# Adafruit_bicolor_8x8.net
KiCad netlist of a schematic drawn in EAGLE
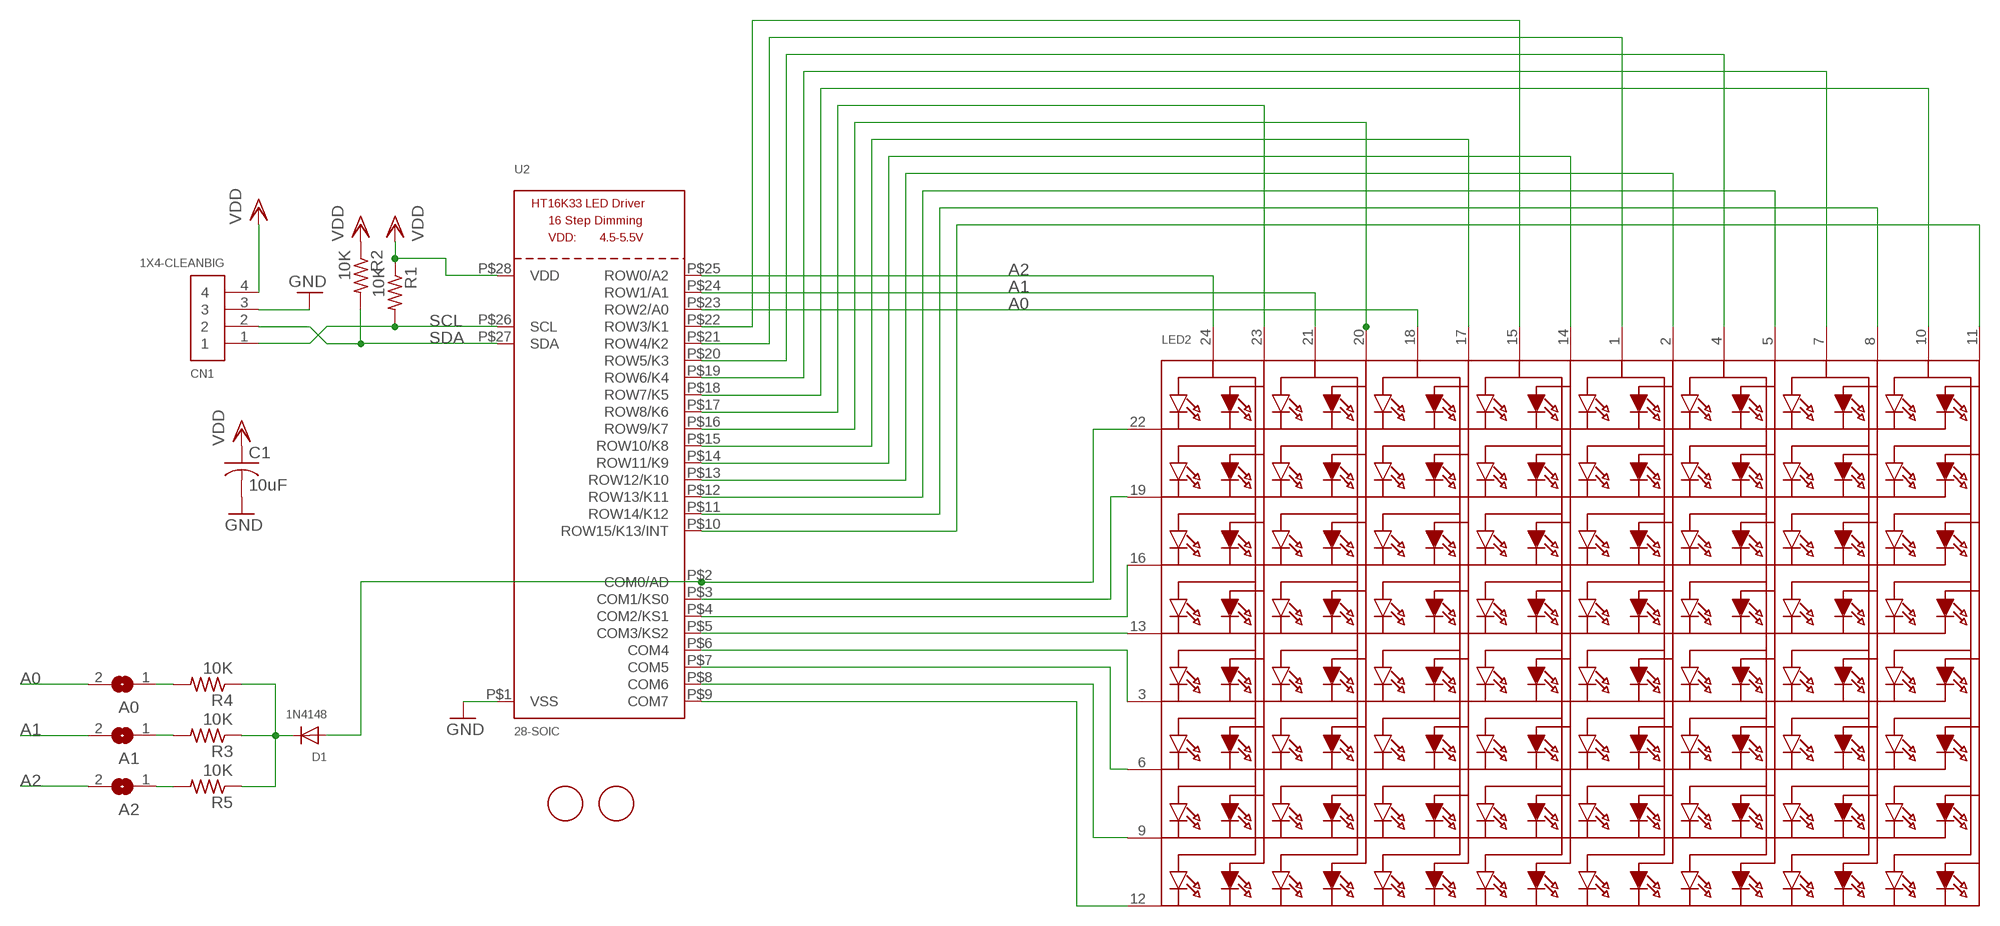
[diagram p0: schematic, sheet 1]

(export (version "E")
  (design (tool "Eeschema 10.0.6"))
  (components
    (comp (ref "A0")
      (value "SOLDERJUMPERREFLOW_NOPASTE")
      (footprint "eagle-import:SOLDERJUMPER_REFLOW_NOPASTE")
      (libsource (lib "eagle-import") (part "SOLDERJUMPERREFLOW_NOPASTE"))
    )
    (comp (ref "A1")
      (value "SOLDERJUMPERREFLOW_NOPASTE")
      (footprint "eagle-import:SOLDERJUMPER_REFLOW_NOPASTE")
      (libsource (lib "eagle-import") (part "SOLDERJUMPERREFLOW_NOPASTE"))
    )
    (comp (ref "A2")
      (value "SOLDERJUMPERREFLOW_NOPASTE")
      (footprint "eagle-import:SOLDERJUMPER_REFLOW_NOPASTE")
      (libsource (lib "eagle-import") (part "SOLDERJUMPERREFLOW_NOPASTE"))
    )
    (comp (ref "C1")
      (value "10uF")
      (footprint "eagle-import:C0805")
      (libsource (lib "eagle-import") (part "C-USC0805"))
    )
    (comp (ref "CN1")
      (value "1X4-CLEANBIG")
      (footprint "eagle-import:1X04-CLEANBIG")
      (libsource (lib "eagle-import") (part "1X4-CLEANBIG"))
    )
    (comp (ref "D1")
      (value "1N4148")
      (footprint "eagle-import:SOD-323F")
      (libsource (lib "eagle-import") (part "DIODESOD-323F"))
    )
    (comp (ref "LED2")
      (value "DISP_SEGMENT_8X8_BICOLOR_ROWCATHODEMI2A883XX")
      (footprint "eagle-import:SEGMENT_BICOL_BL-M12A883XX")
      (libsource (lib "eagle-import") (part "DISP_SEGMENT_8X8_BICOLOR_ROWCATHODEMI2A883XX"))
    )
    (comp (ref "R1")
      (value "10K")
      (footprint "eagle-import:R0805")
      (libsource (lib "eagle-import") (part "R-US_R0805"))
    )
    (comp (ref "R2")
      (value "10K")
      (footprint "eagle-import:R0805")
      (libsource (lib "eagle-import") (part "R-US_R0805"))
    )
    (comp (ref "R3")
      (value "10K")
      (footprint "eagle-import:R0805")
      (libsource (lib "eagle-import") (part "R-US_R0805"))
    )
    (comp (ref "R4")
      (value "10K")
      (footprint "eagle-import:R0805")
      (libsource (lib "eagle-import") (part "R-US_R0805"))
    )
    (comp (ref "R5")
      (value "10K")
      (footprint "eagle-import:R0805")
      (libsource (lib "eagle-import") (part "R-US_R0805"))
    )
    (comp (ref "U$1")
      (value "FIDUCIAL")
      (footprint "eagle-import:FIDUCIAL_1MM")
      (libsource (lib "eagle-import") (part "FIDUCIAL"))
    )
    (comp (ref "U$2")
      (value "FIDUCIAL")
      (footprint "eagle-import:FIDUCIAL_1MM")
      (libsource (lib "eagle-import") (part "FIDUCIAL"))
    )
    (comp (ref "U2")
      (value "28-SOIC")
      (footprint "eagle-import:SOP28_300MIL")
      (libsource (lib "eagle-import") (part "HT16K33_SOP28"))
    )
  )
  (nets
    (net (code "1") (name "/A0") (class "Default")
      (node (ref "A0") (pin "2") (pinfunction "2_2") (pintype "passive"))
      (node (ref "LED2") (pin "18") (pinfunction "A5_18") (pintype "bidirectional"))
      (node (ref "U2") (pin "P$23") (pinfunction "ROW2/A0_P$23") (pintype "bidirectional"))
    )
    (net (code "2") (name "/A1") (class "Default")
      (node (ref "A1") (pin "2") (pinfunction "2_2") (pintype "passive"))
      (node (ref "LED2") (pin "21") (pinfunction "A3_21") (pintype "bidirectional"))
      (node (ref "U2") (pin "P$24") (pinfunction "ROW1/A1_P$24") (pintype "bidirectional"))
    )
    (net (code "3") (name "/A2") (class "Default")
      (node (ref "A2") (pin "2") (pinfunction "2_2") (pintype "passive"))
      (node (ref "LED2") (pin "24") (pinfunction "A1_24") (pintype "bidirectional"))
      (node (ref "U2") (pin "P$25") (pinfunction "ROW0/A2_P$25") (pintype "bidirectional"))
    )
    (net (code "4") (name "/SCL") (class "Default")
      (node (ref "CN1") (pin "1") (pinfunction "1_1") (pintype "bidirectional"))
      (node (ref "R1") (pin "2") (pinfunction "2_2") (pintype "passive"))
      (node (ref "U2") (pin "P$26") (pinfunction "SCL_P$26") (pintype "bidirectional"))
    )
    (net (code "5") (name "/SDA") (class "Default")
      (node (ref "CN1") (pin "2") (pinfunction "2_2") (pintype "bidirectional"))
      (node (ref "R2") (pin "2") (pinfunction "2_2") (pintype "passive"))
      (node (ref "U2") (pin "P$27") (pinfunction "SDA_P$27") (pintype "bidirectional"))
    )
    (net (code "6") (name "GND") (class "Default")
      (node (ref "C1") (pin "2") (pinfunction "2_2") (pintype "passive"))
      (node (ref "CN1") (pin "3") (pinfunction "3_3") (pintype "bidirectional"))
      (node (ref "U2") (pin "P$1") (pinfunction "VSS_P$1") (pintype "bidirectional"))
    )
    (net (code "7") (name "Net-(A0-Pad1)") (class "Default")
      (node (ref "A0") (pin "1") (pinfunction "1_1") (pintype "passive"))
      (node (ref "R4") (pin "2") (pinfunction "2_2") (pintype "passive"))
    )
    (net (code "8") (name "Net-(A1-Pad1)") (class "Default")
      (node (ref "A1") (pin "1") (pinfunction "1_1") (pintype "passive"))
      (node (ref "R3") (pin "2") (pinfunction "2_2") (pintype "passive"))
    )
    (net (code "9") (name "Net-(A2-Pad1)") (class "Default")
      (node (ref "A2") (pin "1") (pinfunction "1_1") (pintype "passive"))
      (node (ref "R5") (pin "2") (pinfunction "2_2") (pintype "passive"))
    )
    (net (code "10") (name "Net-(D1-PadC)") (class "Default")
      (node (ref "D1") (pin "C") (pinfunction "C_C") (pintype "passive"))
      (node (ref "R3") (pin "1") (pinfunction "1_1") (pintype "passive"))
      (node (ref "R4") (pin "1") (pinfunction "1_1") (pintype "passive"))
      (node (ref "R5") (pin "1") (pinfunction "1_1") (pintype "passive"))
    )
    (net (code "11") (name "Net-(LED2-A2)") (class "Default")
      (node (ref "LED2") (pin "23") (pinfunction "A2_23") (pintype "bidirectional"))
      (node (ref "U2") (pin "P$17") (pinfunction "ROW8/K6_P$17") (pintype "bidirectional"))
    )
    (net (code "12") (name "Net-(LED2-A4)") (class "Default")
      (node (ref "LED2") (pin "20") (pinfunction "A4_20") (pintype "bidirectional"))
      (node (ref "U2") (pin "P$16") (pinfunction "ROW9/K7_P$16") (pintype "bidirectional"))
    )
    (net (code "13") (name "Net-(LED2-A6)") (class "Default")
      (node (ref "LED2") (pin "17") (pinfunction "A6_17") (pintype "bidirectional"))
      (node (ref "U2") (pin "P$15") (pinfunction "ROW10/K8_P$15") (pintype "bidirectional"))
    )
    (net (code "14") (name "Net-(LED2-A7)") (class "Default")
      (node (ref "LED2") (pin "15") (pinfunction "A7_15") (pintype "bidirectional"))
      (node (ref "U2") (pin "P$22") (pinfunction "ROW3/K1_P$22") (pintype "bidirectional"))
    )
    (net (code "15") (name "Net-(LED2-A8)") (class "Default")
      (node (ref "LED2") (pin "14") (pinfunction "A8_14") (pintype "bidirectional"))
      (node (ref "U2") (pin "P$14") (pinfunction "ROW11/K9_P$14") (pintype "bidirectional"))
    )
    (net (code "16") (name "Net-(LED2-A9)") (class "Default")
      (node (ref "LED2") (pin "1") (pinfunction "A9_1") (pintype "bidirectional"))
      (node (ref "U2") (pin "P$21") (pinfunction "ROW4/K2_P$21") (pintype "bidirectional"))
    )
    (net (code "17") (name "Net-(LED2-A10)") (class "Default")
      (node (ref "LED2") (pin "2") (pinfunction "A10_2") (pintype "bidirectional"))
      (node (ref "U2") (pin "P$13") (pinfunction "ROW12/K10_P$13") (pintype "bidirectional"))
    )
    (net (code "18") (name "Net-(LED2-A11)") (class "Default")
      (node (ref "LED2") (pin "4") (pinfunction "A11_4") (pintype "bidirectional"))
      (node (ref "U2") (pin "P$20") (pinfunction "ROW5/K3_P$20") (pintype "bidirectional"))
    )
    (net (code "19") (name "Net-(LED2-A12)") (class "Default")
      (node (ref "LED2") (pin "5") (pinfunction "A12_5") (pintype "bidirectional"))
      (node (ref "U2") (pin "P$12") (pinfunction "ROW13/K11_P$12") (pintype "bidirectional"))
    )
    (net (code "20") (name "Net-(LED2-A13)") (class "Default")
      (node (ref "LED2") (pin "7") (pinfunction "A13_7") (pintype "bidirectional"))
      (node (ref "U2") (pin "P$19") (pinfunction "ROW6/K4_P$19") (pintype "bidirectional"))
    )
    (net (code "21") (name "Net-(LED2-A14)") (class "Default")
      (node (ref "LED2") (pin "8") (pinfunction "A14_8") (pintype "bidirectional"))
      (node (ref "U2") (pin "P$11") (pinfunction "ROW14/K12_P$11") (pintype "bidirectional"))
    )
    (net (code "22") (name "Net-(LED2-A15)") (class "Default")
      (node (ref "LED2") (pin "10") (pinfunction "A15_10") (pintype "bidirectional"))
      (node (ref "U2") (pin "P$18") (pinfunction "ROW7/K5_P$18") (pintype "bidirectional"))
    )
    (net (code "23") (name "Net-(LED2-A16)") (class "Default")
      (node (ref "LED2") (pin "11") (pinfunction "A16_11") (pintype "bidirectional"))
      (node (ref "U2") (pin "P$10") (pinfunction "ROW15/K13/INT_P$10") (pintype "bidirectional"))
    )
    (net (code "24") (name "Net-(LED2-K1)") (class "Default")
      (node (ref "D1") (pin "A") (pinfunction "A_A") (pintype "passive"))
      (node (ref "LED2") (pin "22") (pinfunction "K1_22") (pintype "bidirectional"))
      (node (ref "U2") (pin "P$2") (pinfunction "COM0/AD_P$2") (pintype "bidirectional"))
    )
    (net (code "25") (name "Net-(LED2-K2)") (class "Default")
      (node (ref "LED2") (pin "19") (pinfunction "K2_19") (pintype "bidirectional"))
      (node (ref "U2") (pin "P$3") (pinfunction "COM1/KS0_P$3") (pintype "bidirectional"))
    )
    (net (code "26") (name "Net-(LED2-K3)") (class "Default")
      (node (ref "LED2") (pin "16") (pinfunction "K3_16") (pintype "bidirectional"))
      (node (ref "U2") (pin "P$4") (pinfunction "COM2/KS1_P$4") (pintype "bidirectional"))
    )
    (net (code "27") (name "Net-(LED2-K4)") (class "Default")
      (node (ref "LED2") (pin "13") (pinfunction "K4_13") (pintype "bidirectional"))
      (node (ref "U2") (pin "P$5") (pinfunction "COM3/KS2_P$5") (pintype "bidirectional"))
    )
    (net (code "28") (name "Net-(LED2-K5)") (class "Default")
      (node (ref "LED2") (pin "3") (pinfunction "K5_3") (pintype "bidirectional"))
      (node (ref "U2") (pin "P$6") (pinfunction "COM4_P$6") (pintype "bidirectional"))
    )
    (net (code "29") (name "Net-(LED2-K6)") (class "Default")
      (node (ref "LED2") (pin "6") (pinfunction "K6_6") (pintype "bidirectional"))
      (node (ref "U2") (pin "P$7") (pinfunction "COM5_P$7") (pintype "bidirectional"))
    )
    (net (code "30") (name "Net-(LED2-K7)") (class "Default")
      (node (ref "LED2") (pin "9") (pinfunction "K7_9") (pintype "bidirectional"))
      (node (ref "U2") (pin "P$8") (pinfunction "COM6_P$8") (pintype "bidirectional"))
    )
    (net (code "31") (name "Net-(LED2-K8)") (class "Default")
      (node (ref "LED2") (pin "12") (pinfunction "K8_12") (pintype "bidirectional"))
      (node (ref "U2") (pin "P$9") (pinfunction "COM7_P$9") (pintype "bidirectional"))
    )
    (net (code "32") (name "VDD") (class "Default")
      (node (ref "C1") (pin "1") (pinfunction "1_1") (pintype "passive"))
      (node (ref "CN1") (pin "4") (pinfunction "4_4") (pintype "bidirectional"))
      (node (ref "R1") (pin "1") (pinfunction "1_1") (pintype "passive"))
      (node (ref "R2") (pin "1") (pinfunction "1_1") (pintype "passive"))
      (node (ref "U2") (pin "P$28") (pinfunction "VDD_P$28") (pintype "bidirectional"))
    )
  )
)
